# CNY70.net
KiCad netlist of a schematic drawn in EAGLE
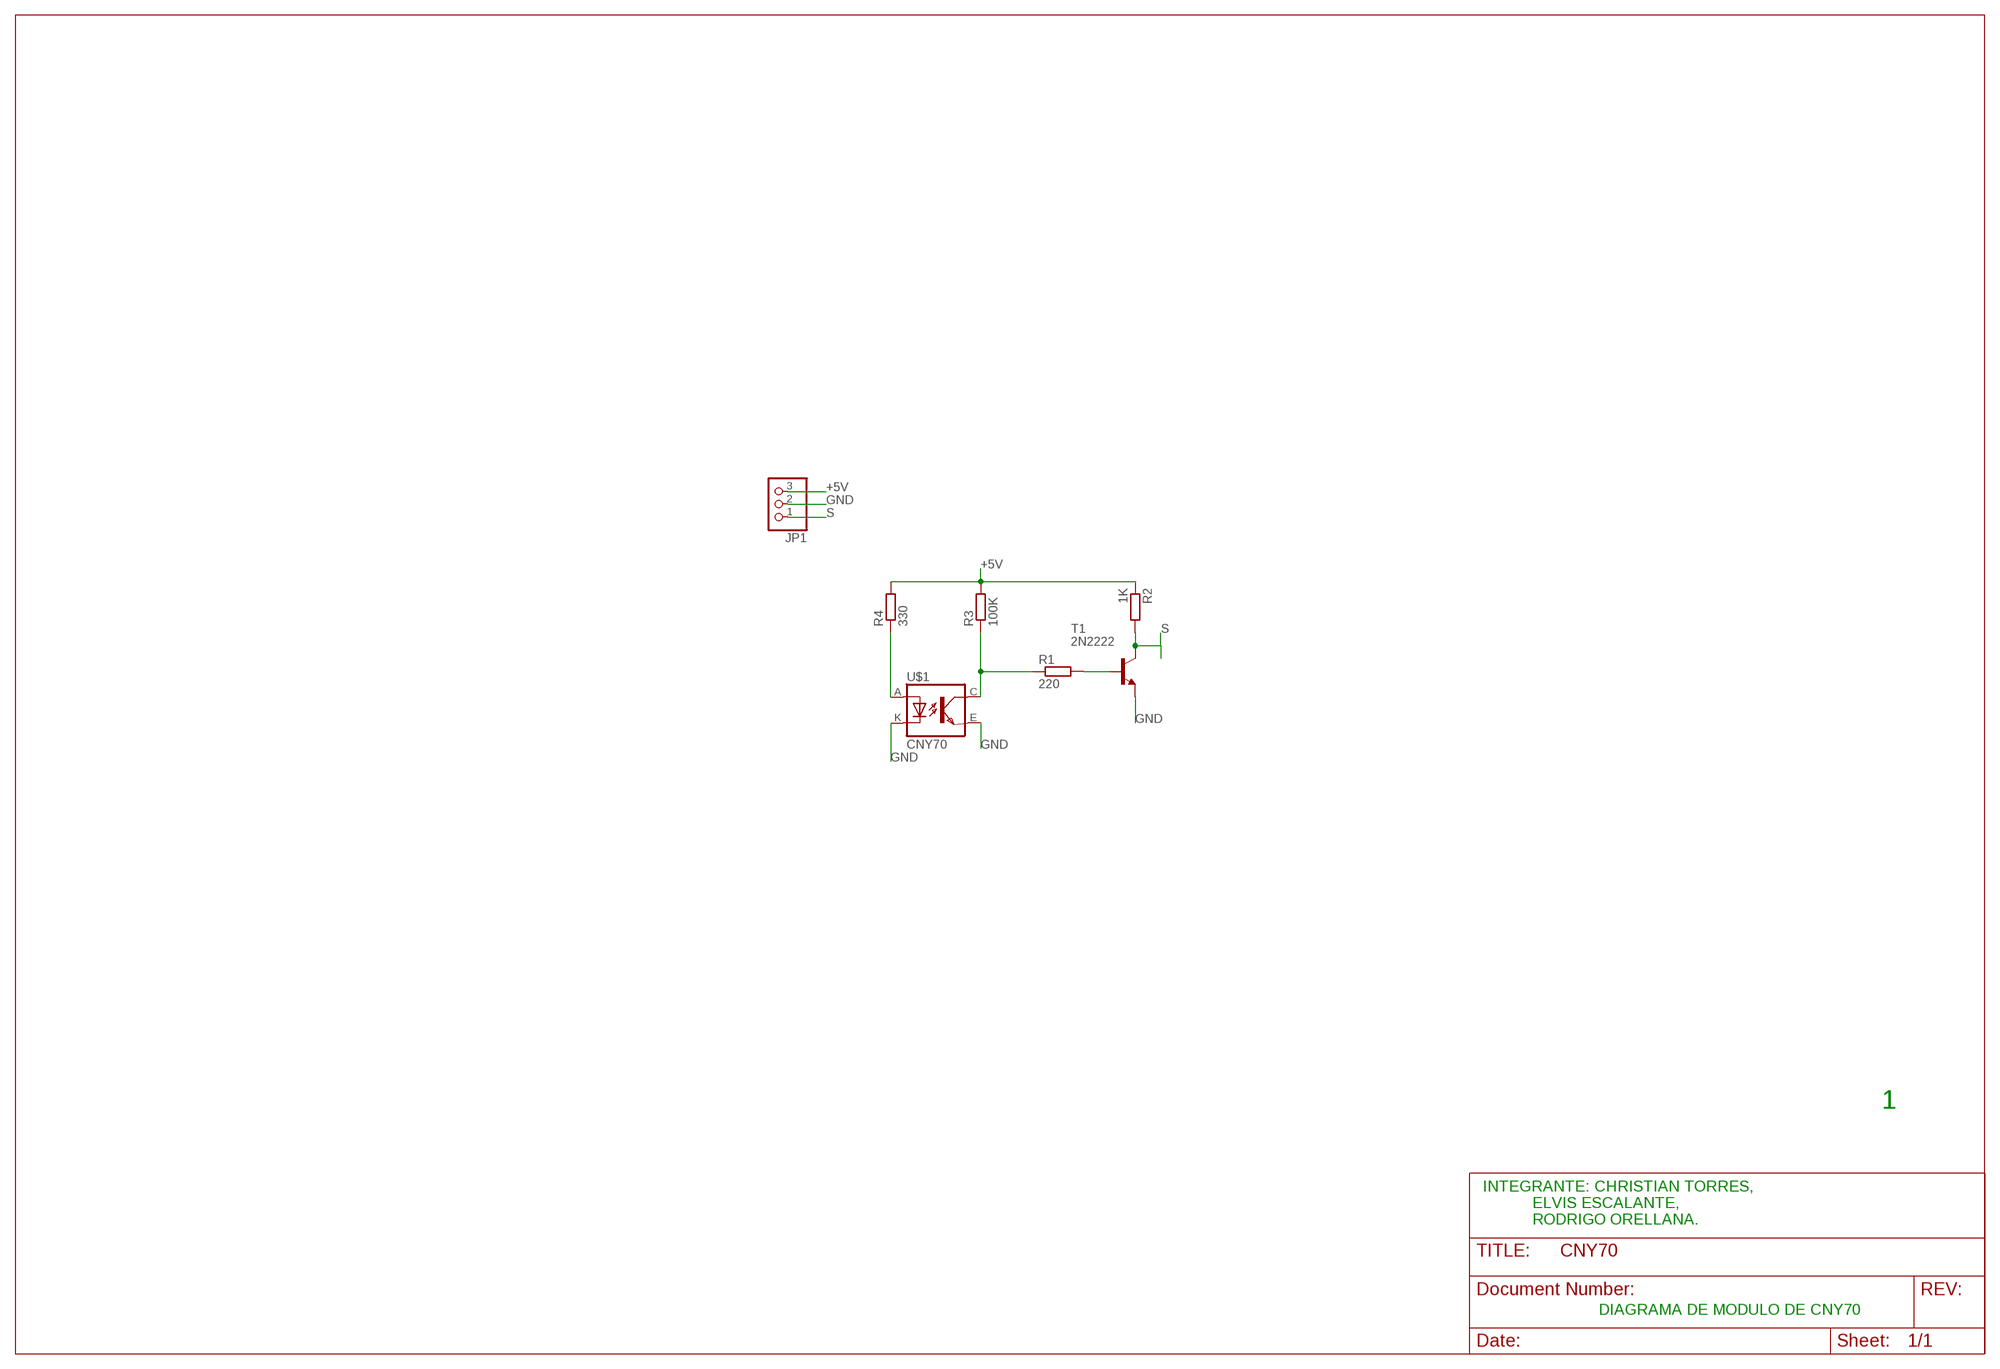
[diagram p0: schematic, sheet 1]

(export (version "E")
  (design (tool "Eeschema 10.0.6"))
  (components
    (comp (ref "JP1")
      (value "PINHD-1X3")
      (footprint "eagle-import:1X03")
      (libsource (lib "eagle-import") (part "PINHD-1X3"))
    )
    (comp (ref "R1")
      (value "220")
      (footprint "eagle-import:0207_12")
      (libsource (lib "eagle-import") (part "R-EU_0207/12"))
    )
    (comp (ref "R2")
      (value "1K")
      (footprint "eagle-import:0207_12")
      (libsource (lib "eagle-import") (part "R-EU_0207/12"))
    )
    (comp (ref "R3")
      (value "100K")
      (footprint "eagle-import:0207_12")
      (libsource (lib "eagle-import") (part "R-EU_0207/12"))
    )
    (comp (ref "R4")
      (value "330")
      (footprint "eagle-import:0207_12")
      (libsource (lib "eagle-import") (part "R-EU_0207/12"))
    )
    (comp (ref "T1")
      (value "2N2222")
      (footprint "eagle-import:TO92")
      (libsource (lib "eagle-import") (part "2N2222"))
    )
    (comp (ref "U$1")
      (value "CNY70")
      (footprint "eagle-import:4")
      (libsource (lib "eagle-import") (part "CNY70"))
    )
  )
  (nets
    (net (code "1") (name "/+5V") (class "Default")
      (node (ref "JP1") (pin "3") (pinfunction "3_3") (pintype "passive"))
      (node (ref "R2") (pin "1") (pinfunction "1_1") (pintype "passive"))
      (node (ref "R3") (pin "2") (pinfunction "2_2") (pintype "passive"))
      (node (ref "R4") (pin "2") (pinfunction "2_2") (pintype "passive"))
    )
    (net (code "2") (name "/GND") (class "Default")
      (node (ref "JP1") (pin "2") (pinfunction "2_2") (pintype "passive"))
      (node (ref "T1") (pin "3") (pinfunction "E_3") (pintype "passive"))
      (node (ref "U$1") (pin "E") (pinfunction "EMI_E") (pintype "passive"))
      (node (ref "U$1") (pin "K") (pinfunction "C_K") (pintype "passive"))
    )
    (net (code "3") (name "/S") (class "Default")
      (node (ref "JP1") (pin "1") (pinfunction "1_1") (pintype "passive"))
      (node (ref "R2") (pin "2") (pinfunction "2_2") (pintype "passive"))
      (node (ref "T1") (pin "2") (pinfunction "C_2") (pintype "passive"))
    )
    (net (code "4") (name "Net-(R4-Pad1)") (class "Default")
      (node (ref "R4") (pin "1") (pinfunction "1_1") (pintype "passive"))
      (node (ref "U$1") (pin "A") (pinfunction "A_A") (pintype "passive"))
    )
    (net (code "5") (name "Net-(T1-B)") (class "Default")
      (node (ref "R1") (pin "2") (pinfunction "2_2") (pintype "passive"))
      (node (ref "T1") (pin "1") (pinfunction "B_1") (pintype "passive"))
    )
    (net (code "6") (name "Net-(U$1-COL)") (class "Default")
      (node (ref "R1") (pin "1") (pinfunction "1_1") (pintype "passive"))
      (node (ref "R3") (pin "1") (pinfunction "1_1") (pintype "passive"))
      (node (ref "U$1") (pin "C") (pinfunction "COL_C") (pintype "passive"))
    )
  )
)
